# Aula_1_-_Oscilador_Ast_vel.net
KiCad netlist of a schematic drawn in EAGLE
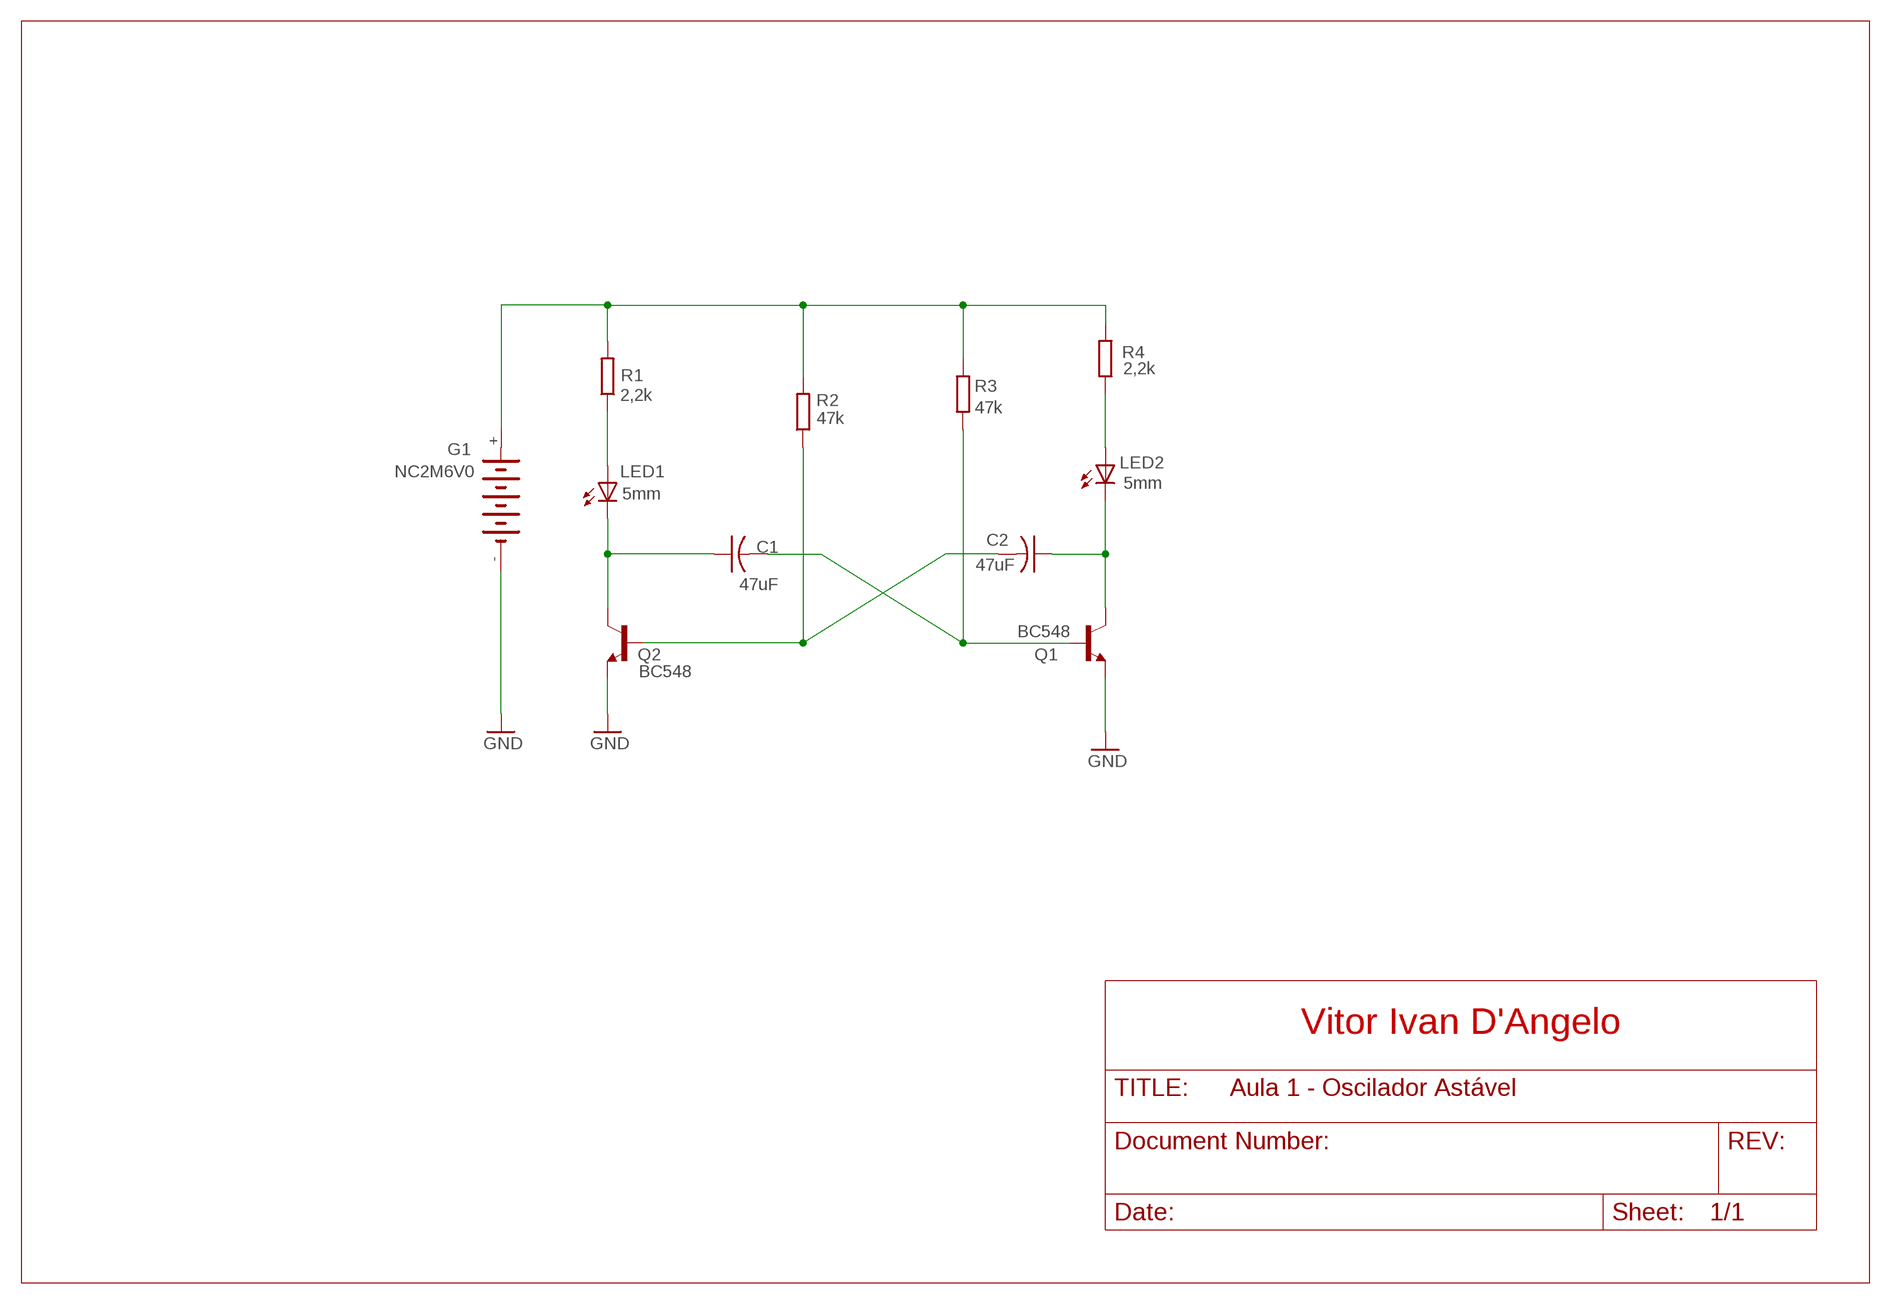
[diagram p0: schematic, sheet 1]

(export (version "E")
  (design (tool "Eeschema 10.0.6"))
  (components
    (comp (ref "C1")
      (value "47uF")
      (footprint "eagle-import:C025-025X050")
      (libsource (lib "eagle-import") (part "C-US025-025X050"))
    )
    (comp (ref "C2")
      (value "47uF")
      (footprint "eagle-import:C025-025X050")
      (libsource (lib "eagle-import") (part "C-US025-025X050"))
    )
    (comp (ref "G1")
      (value "NC2M6V0")
      (footprint "eagle-import:NC2M")
      (libsource (lib "eagle-import") (part "NC2M6V0"))
    )
    (comp (ref "LED1")
      (value "5mm")
      (footprint "eagle-import:LED5MM")
      (libsource (lib "eagle-import") (part "LED5MM"))
    )
    (comp (ref "LED2")
      (value "5mm")
      (footprint "eagle-import:LED5MM")
      (libsource (lib "eagle-import") (part "LED5MM"))
    )
    (comp (ref "Q1")
      (value "BC548")
      (footprint "eagle-import:TO92-EBC")
      (libsource (lib "eagle-import") (part "BC548"))
    )
    (comp (ref "Q2")
      (value "BC548")
      (footprint "eagle-import:TO92-EBC")
      (libsource (lib "eagle-import") (part "BC548"))
    )
    (comp (ref "R1")
      (value "2,2k")
      (footprint "eagle-import:0204_5")
      (libsource (lib "eagle-import") (part "R-EU_0204/5"))
    )
    (comp (ref "R2")
      (value "47k")
      (footprint "eagle-import:0204_5")
      (libsource (lib "eagle-import") (part "R-EU_0204/5"))
    )
    (comp (ref "R3")
      (value "47k")
      (footprint "eagle-import:0204_5")
      (libsource (lib "eagle-import") (part "R-EU_0204/5"))
    )
    (comp (ref "R4")
      (value "2,2k")
      (footprint "eagle-import:0204_5")
      (libsource (lib "eagle-import") (part "R-EU_0204/5"))
    )
  )
  (nets
    (net (code "1") (name "GND") (class "Default")
      (node (ref "G1") (pin "-") (pinfunction "-_-") (pintype "passive"))
      (node (ref "Q1") (pin "E") (pinfunction "E_E") (pintype "passive"))
      (node (ref "Q2") (pin "E") (pinfunction "E_E") (pintype "passive"))
    )
    (net (code "2") (name "Net-(C1-Pad2)") (class "Default")
      (node (ref "C1") (pin "2") (pinfunction "2_2") (pintype "passive"))
      (node (ref "Q1") (pin "B") (pinfunction "B_B") (pintype "passive"))
      (node (ref "R3") (pin "1") (pinfunction "1_1") (pintype "passive"))
    )
    (net (code "3") (name "Net-(C2-Pad2)") (class "Default")
      (node (ref "C2") (pin "2") (pinfunction "2_2") (pintype "passive"))
      (node (ref "Q2") (pin "B") (pinfunction "B_B") (pintype "passive"))
      (node (ref "R2") (pin "1") (pinfunction "1_1") (pintype "passive"))
    )
    (net (code "4") (name "Net-(G1-Pad+)") (class "Default")
      (node (ref "G1") (pin "+") (pinfunction "+_+") (pintype "passive"))
      (node (ref "R1") (pin "2") (pinfunction "2_2") (pintype "passive"))
      (node (ref "R2") (pin "2") (pinfunction "2_2") (pintype "passive"))
      (node (ref "R3") (pin "2") (pinfunction "2_2") (pintype "passive"))
      (node (ref "R4") (pin "2") (pinfunction "2_2") (pintype "passive"))
    )
    (net (code "5") (name "Net-(LED1-C)") (class "Default")
      (node (ref "C1") (pin "1") (pinfunction "1_1") (pintype "passive"))
      (node (ref "LED1") (pin "K") (pinfunction "C_K") (pintype "passive"))
      (node (ref "Q2") (pin "C") (pinfunction "C_C") (pintype "passive"))
    )
    (net (code "6") (name "Net-(LED1-PadA)") (class "Default")
      (node (ref "LED1") (pin "A") (pinfunction "A_A") (pintype "passive"))
      (node (ref "R1") (pin "1") (pinfunction "1_1") (pintype "passive"))
    )
    (net (code "7") (name "Net-(LED2-C)") (class "Default")
      (node (ref "C2") (pin "1") (pinfunction "1_1") (pintype "passive"))
      (node (ref "LED2") (pin "K") (pinfunction "C_K") (pintype "passive"))
      (node (ref "Q1") (pin "C") (pinfunction "C_C") (pintype "passive"))
    )
    (net (code "8") (name "Net-(LED2-PadA)") (class "Default")
      (node (ref "LED2") (pin "A") (pinfunction "A_A") (pintype "passive"))
      (node (ref "R4") (pin "1") (pinfunction "1_1") (pintype "passive"))
    )
    (net (code "9") (name "unconnected-(G1-+-Pad+@1)") (class "Default")
      (node (ref "G1") (pin "+@1") (pinfunction "+_+@1") (pintype "passive"))
    )
  )
)
